# vera-module.net
KiCad netlist of a schematic drawn in EAGLE
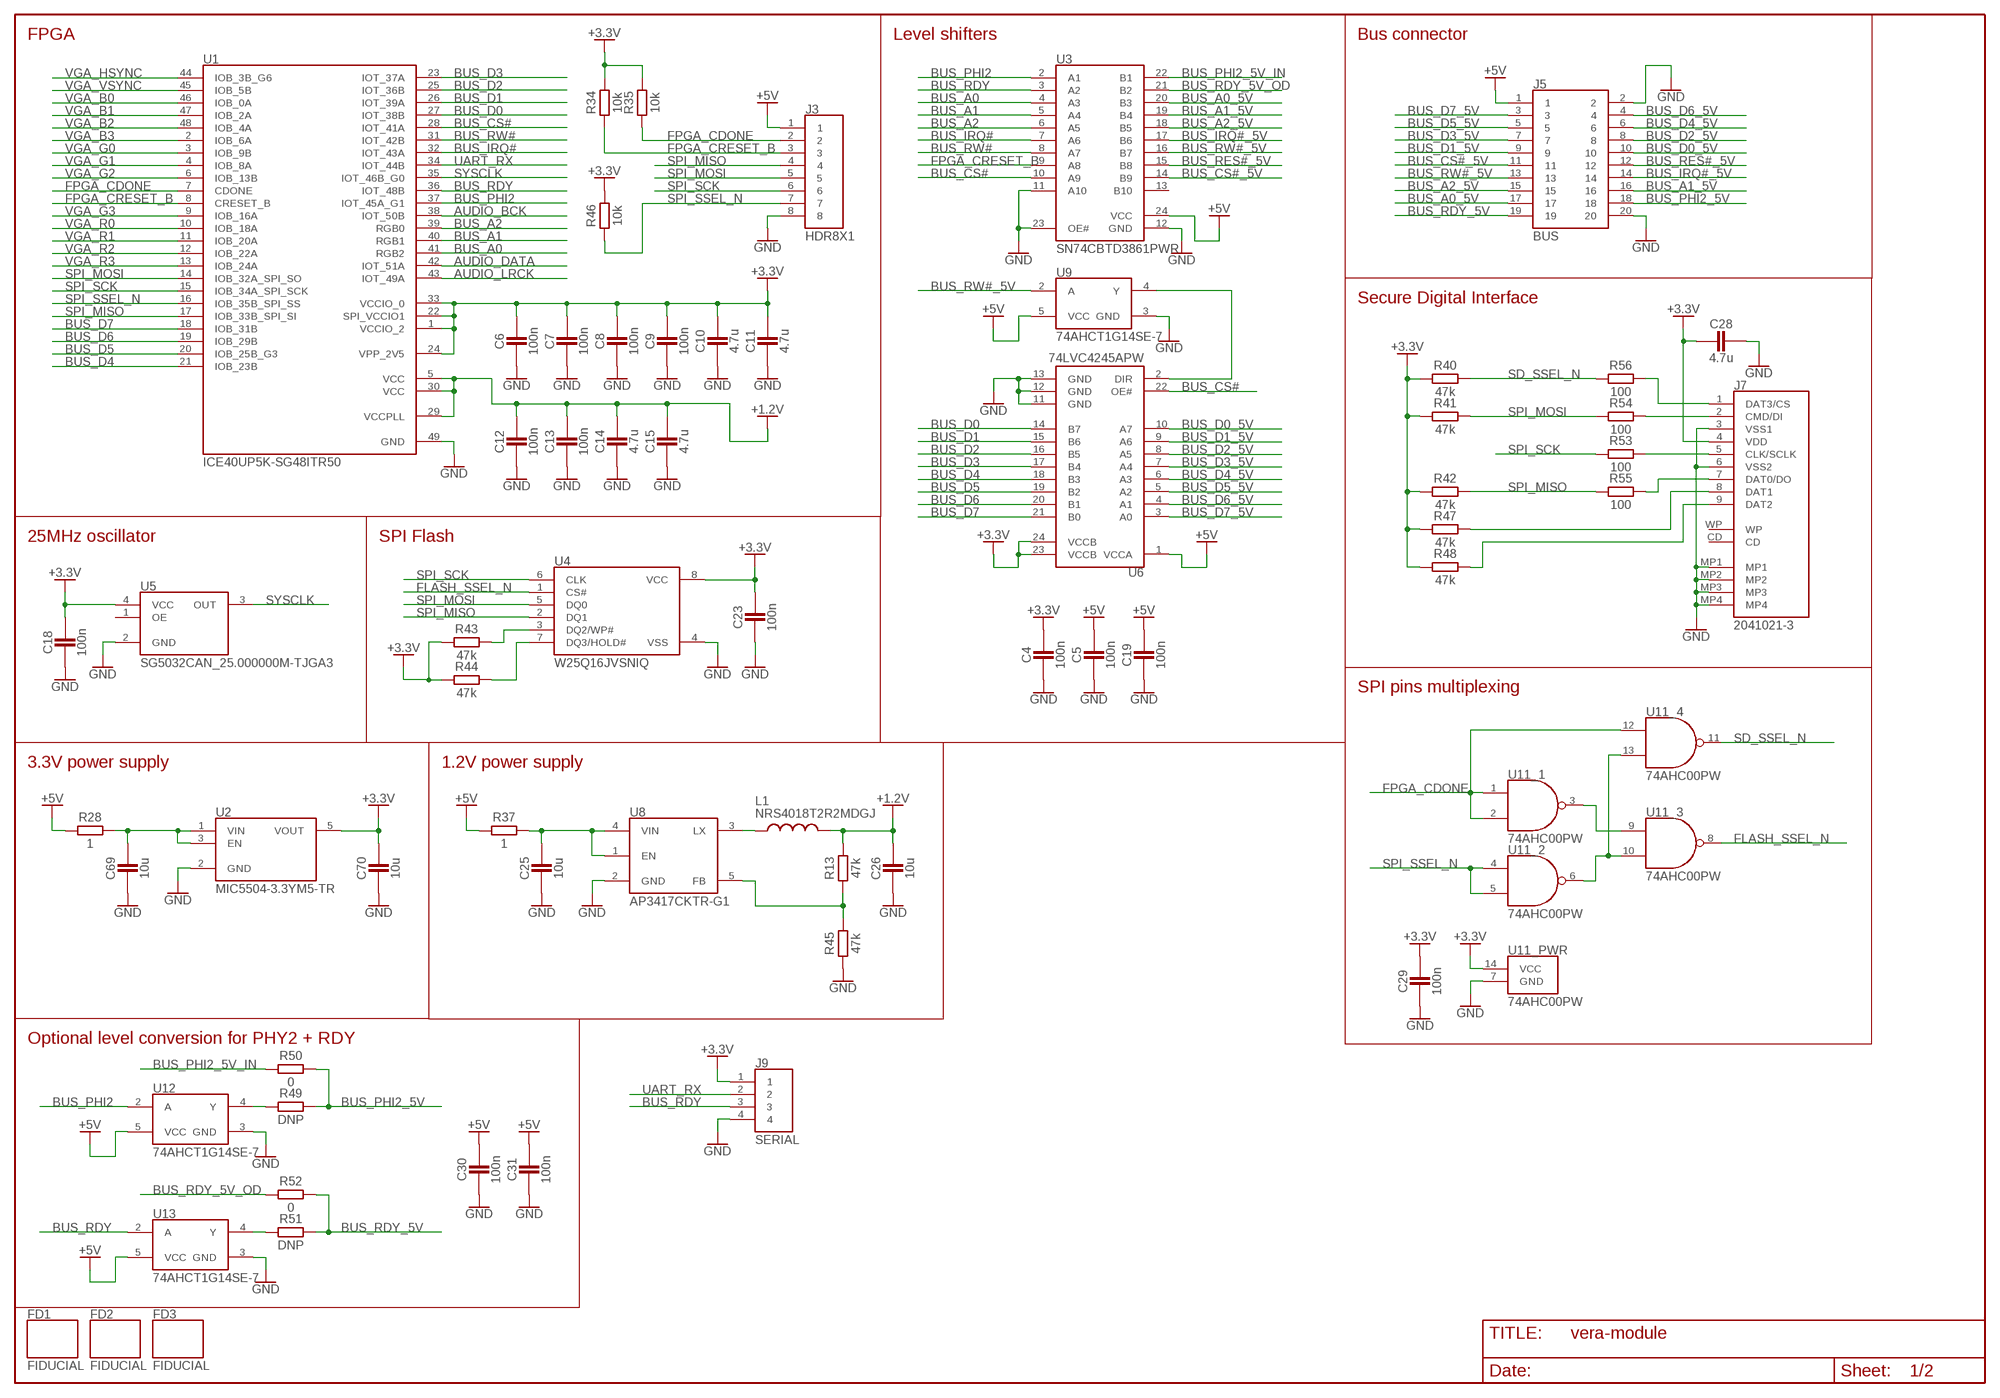
[diagram p0: schematic, sheet 1]
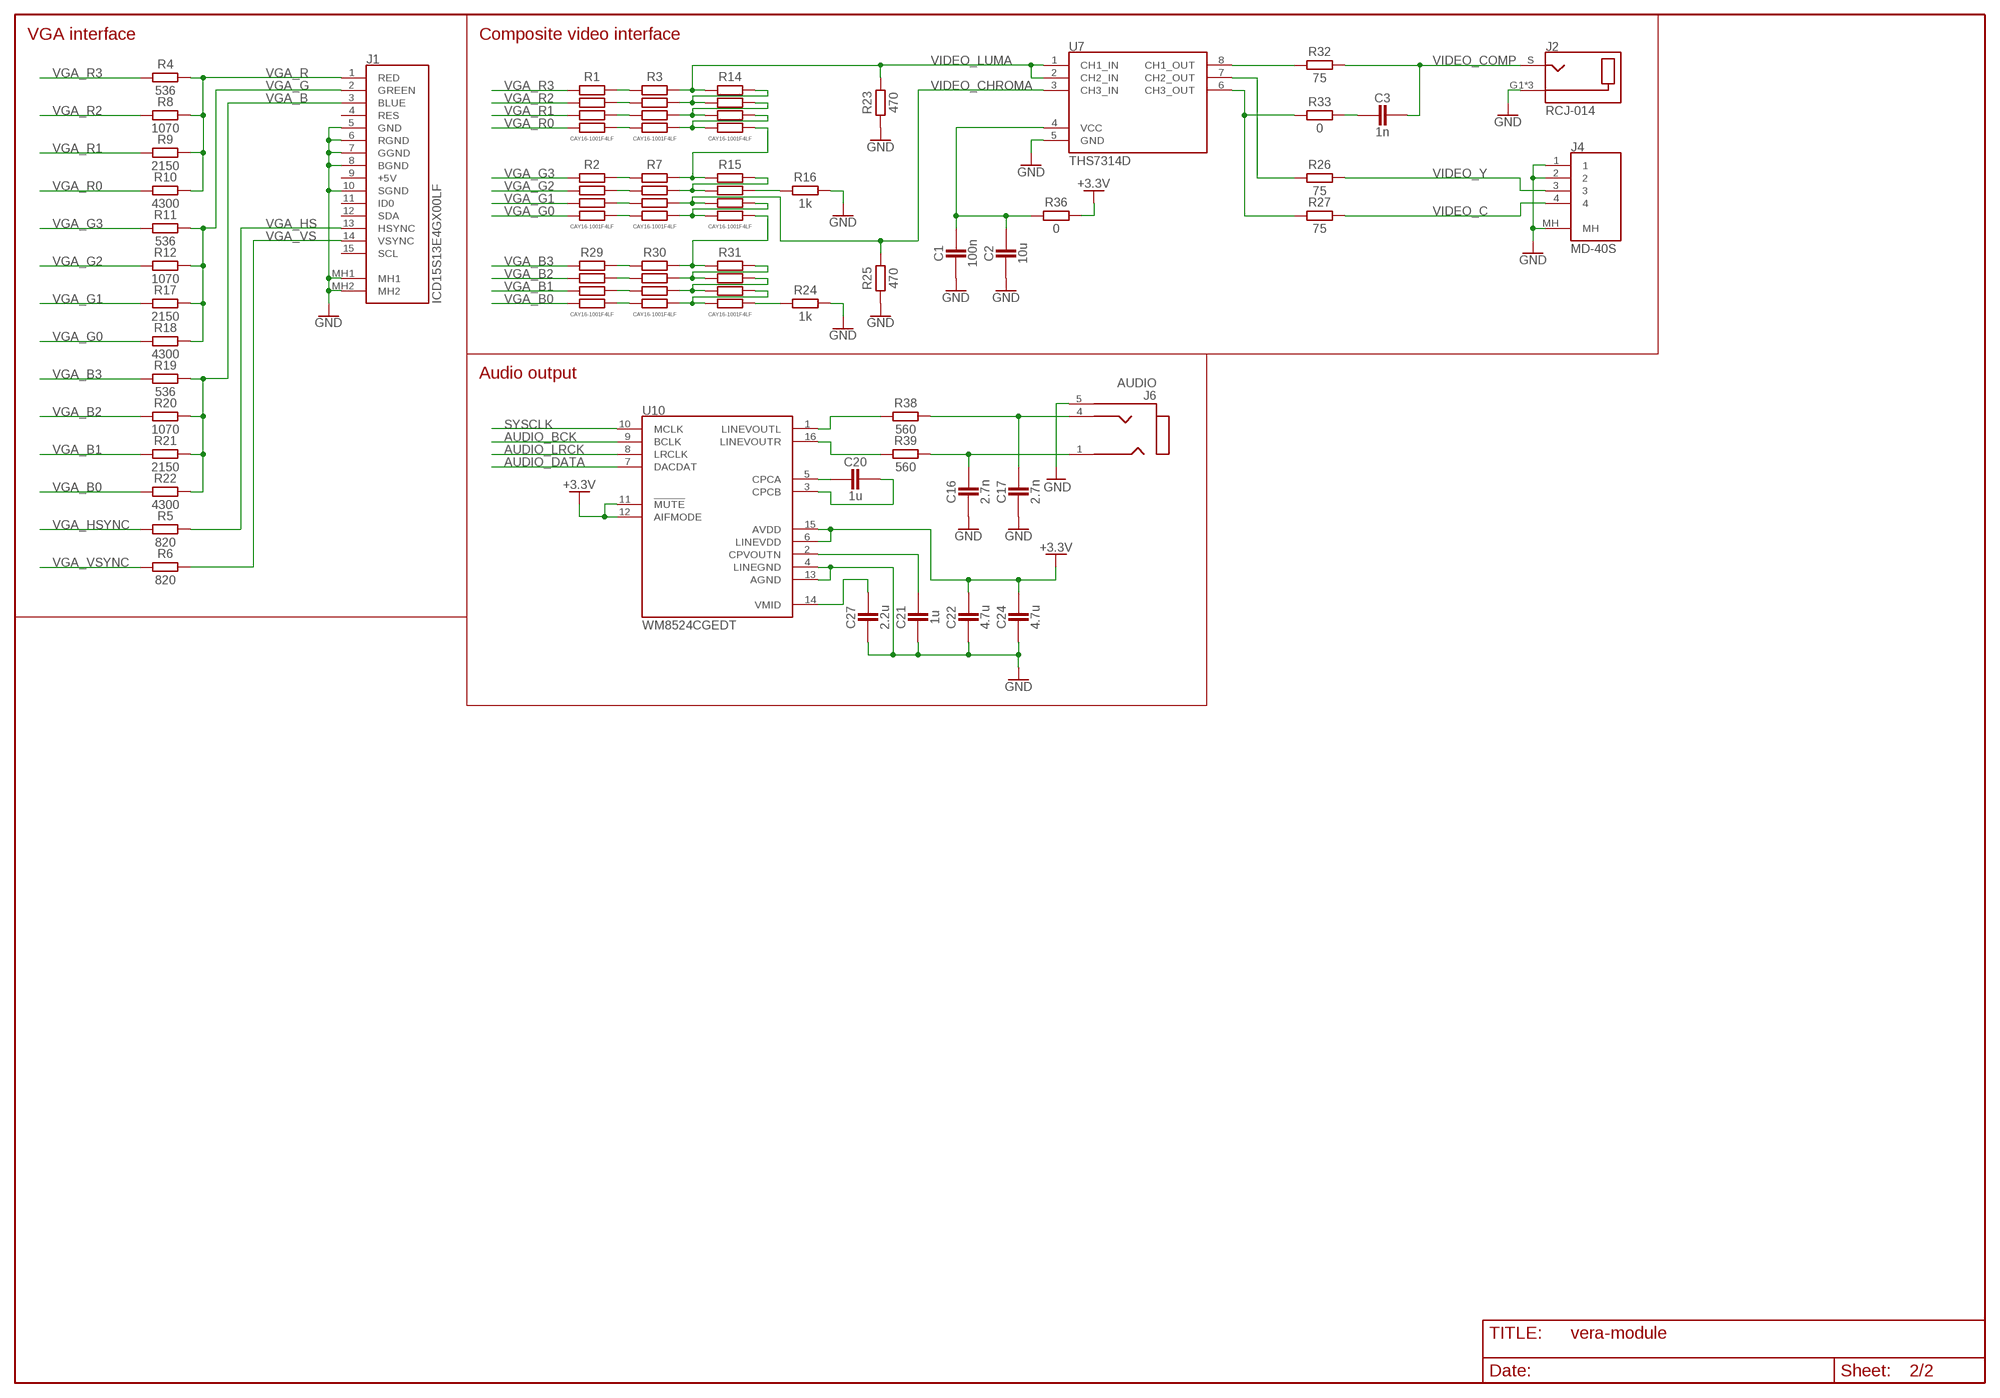
[diagram p1: schematic, sheet 2]

(export (version "E")
  (design (tool "Eeschema 10.0.6"))
  (components
    (comp (ref "C1")
      (value "100n")
      (footprint "eagle-import:C0603")
      (libsource (lib "eagle-import") (part "CAPACITOR0603"))
    )
    (comp (ref "C2")
      (value "10u")
      (footprint "eagle-import:C0805")
      (libsource (lib "eagle-import") (part "CAPACITOR0805"))
    )
    (comp (ref "C3")
      (value "1n")
      (footprint "eagle-import:C0603")
      (libsource (lib "eagle-import") (part "CAPACITOR0603"))
    )
    (comp (ref "C16")
      (value "2.7n")
      (footprint "eagle-import:C0603")
      (libsource (lib "eagle-import") (part "CAPACITOR0603"))
    )
    (comp (ref "C17")
      (value "2.7n")
      (footprint "eagle-import:C0603")
      (libsource (lib "eagle-import") (part "CAPACITOR0603"))
    )
    (comp (ref "C20")
      (value "1u")
      (footprint "eagle-import:C0603")
      (libsource (lib "eagle-import") (part "CAPACITOR0603"))
    )
    (comp (ref "C21")
      (value "1u")
      (footprint "eagle-import:C0603")
      (libsource (lib "eagle-import") (part "CAPACITOR0603"))
    )
    (comp (ref "C22")
      (value "4.7u")
      (footprint "eagle-import:C0603")
      (libsource (lib "eagle-import") (part "CAPACITOR0603"))
    )
    (comp (ref "C24")
      (value "4.7u")
      (footprint "eagle-import:C0603")
      (libsource (lib "eagle-import") (part "CAPACITOR0603"))
    )
    (comp (ref "C27")
      (value "2.2u")
      (footprint "eagle-import:C0603")
      (libsource (lib "eagle-import") (part "CAPACITOR0603"))
    )
    (comp (ref "J1")
      (value "ICD15S13E4GX00LF")
      (footprint "eagle-import:1-1734344-2")
      (libsource (lib "eagle-import") (part "ICD15S13E4GX00LF"))
    )
    (comp (ref "J2")
      (value "RCJ-014")
      (footprint "eagle-import:RCJ-01X")
      (libsource (lib "eagle-import") (part "RCJ-014"))
    )
    (comp (ref "J4")
      (value "MD-40S")
      (footprint "eagle-import:MD-40S")
      (libsource (lib "eagle-import") (part "MD-40S"))
    )
    (comp (ref "J6")
      (value "AUDIO")
      (footprint "eagle-import:35RASMT2BHNTRX")
      (libsource (lib "eagle-import") (part "35RASMT2BHNTRX"))
    )
    (comp (ref "R1")
      (value "CAY16-1001F4LF")
      (footprint "eagle-import:RA4_1206")
      (libsource (lib "eagle-import") (part "RES_ARRAY41206"))
    )
    (comp (ref "R2")
      (value "CAY16-1001F4LF")
      (footprint "eagle-import:RA4_1206")
      (libsource (lib "eagle-import") (part "RES_ARRAY41206"))
    )
    (comp (ref "R3")
      (value "CAY16-1001F4LF")
      (footprint "eagle-import:RA4_1206")
      (libsource (lib "eagle-import") (part "RES_ARRAY41206"))
    )
    (comp (ref "R4")
      (value "536")
      (footprint "eagle-import:R0603")
      (libsource (lib "eagle-import") (part "RESISTOR0603"))
    )
    (comp (ref "R5")
      (value "820")
      (footprint "eagle-import:R0603")
      (libsource (lib "eagle-import") (part "RESISTOR0603"))
    )
    (comp (ref "R6")
      (value "820")
      (footprint "eagle-import:R0603")
      (libsource (lib "eagle-import") (part "RESISTOR0603"))
    )
    (comp (ref "R7")
      (value "CAY16-1001F4LF")
      (footprint "eagle-import:RA4_1206")
      (libsource (lib "eagle-import") (part "RES_ARRAY41206"))
    )
    (comp (ref "R8")
      (value "1070")
      (footprint "eagle-import:R0603")
      (libsource (lib "eagle-import") (part "RESISTOR0603"))
    )
    (comp (ref "R9")
      (value "2150")
      (footprint "eagle-import:R0603")
      (libsource (lib "eagle-import") (part "RESISTOR0603"))
    )
    (comp (ref "R10")
      (value "4300")
      (footprint "eagle-import:R0603")
      (libsource (lib "eagle-import") (part "RESISTOR0603"))
    )
    (comp (ref "R11")
      (value "536")
      (footprint "eagle-import:R0603")
      (libsource (lib "eagle-import") (part "RESISTOR0603"))
    )
    (comp (ref "R12")
      (value "1070")
      (footprint "eagle-import:R0603")
      (libsource (lib "eagle-import") (part "RESISTOR0603"))
    )
    (comp (ref "R14")
      (value "CAY16-1001F4LF")
      (footprint "eagle-import:RA4_1206")
      (libsource (lib "eagle-import") (part "RES_ARRAY41206"))
    )
    (comp (ref "R15")
      (value "CAY16-1001F4LF")
      (footprint "eagle-import:RA4_1206")
      (libsource (lib "eagle-import") (part "RES_ARRAY41206"))
    )
    (comp (ref "R16")
      (value "1k")
      (footprint "eagle-import:R0603")
      (libsource (lib "eagle-import") (part "RESISTOR0603"))
    )
    (comp (ref "R17")
      (value "2150")
      (footprint "eagle-import:R0603")
      (libsource (lib "eagle-import") (part "RESISTOR0603"))
    )
    (comp (ref "R18")
      (value "4300")
      (footprint "eagle-import:R0603")
      (libsource (lib "eagle-import") (part "RESISTOR0603"))
    )
    (comp (ref "R19")
      (value "536")
      (footprint "eagle-import:R0603")
      (libsource (lib "eagle-import") (part "RESISTOR0603"))
    )
    (comp (ref "R20")
      (value "1070")
      (footprint "eagle-import:R0603")
      (libsource (lib "eagle-import") (part "RESISTOR0603"))
    )
    (comp (ref "R21")
      (value "2150")
      (footprint "eagle-import:R0603")
      (libsource (lib "eagle-import") (part "RESISTOR0603"))
    )
    (comp (ref "R22")
      (value "4300")
      (footprint "eagle-import:R0603")
      (libsource (lib "eagle-import") (part "RESISTOR0603"))
    )
    (comp (ref "R23")
      (value "470")
      (footprint "eagle-import:R0603")
      (libsource (lib "eagle-import") (part "RESISTOR0603"))
    )
    (comp (ref "R24")
      (value "1k")
      (footprint "eagle-import:R0603")
      (libsource (lib "eagle-import") (part "RESISTOR0603"))
    )
    (comp (ref "R25")
      (value "470")
      (footprint "eagle-import:R0603")
      (libsource (lib "eagle-import") (part "RESISTOR0603"))
    )
    (comp (ref "R26")
      (value "75")
      (footprint "eagle-import:R0603")
      (libsource (lib "eagle-import") (part "RESISTOR0603"))
    )
    (comp (ref "R27")
      (value "75")
      (footprint "eagle-import:R0603")
      (libsource (lib "eagle-import") (part "RESISTOR0603"))
    )
    (comp (ref "R29")
      (value "CAY16-1001F4LF")
      (footprint "eagle-import:RA4_1206")
      (libsource (lib "eagle-import") (part "RES_ARRAY41206"))
    )
    (comp (ref "R30")
      (value "CAY16-1001F4LF")
      (footprint "eagle-import:RA4_1206")
      (libsource (lib "eagle-import") (part "RES_ARRAY41206"))
    )
    (comp (ref "R31")
      (value "CAY16-1001F4LF")
      (footprint "eagle-import:RA4_1206")
      (libsource (lib "eagle-import") (part "RES_ARRAY41206"))
    )
    (comp (ref "R32")
      (value "75")
      (footprint "eagle-import:R0603")
      (libsource (lib "eagle-import") (part "RESISTOR0603"))
    )
    (comp (ref "R33")
      (value "0")
      (footprint "eagle-import:R0603")
      (libsource (lib "eagle-import") (part "RESISTOR0603"))
    )
    (comp (ref "R36")
      (value "0")
      (footprint "eagle-import:R0603")
      (libsource (lib "eagle-import") (part "RESISTOR0603"))
    )
    (comp (ref "R38")
      (value "560")
      (footprint "eagle-import:R0603")
      (libsource (lib "eagle-import") (part "RESISTOR0603"))
    )
    (comp (ref "R39")
      (value "560")
      (footprint "eagle-import:R0603")
      (libsource (lib "eagle-import") (part "RESISTOR0603"))
    )
    (comp (ref "U7")
      (value "THS7314D")
      (footprint "eagle-import:SOIC-8")
      (libsource (lib "eagle-import") (part "THS7314D"))
    )
    (comp (ref "U10")
      (value "WM8524CGEDT")
      (footprint "eagle-import:TSSOP-16")
      (libsource (lib "eagle-import") (part "WM8524CGEDT"))
    )
    (comp (ref "C4")
      (value "100n")
      (footprint "eagle-import:C0603")
      (libsource (lib "eagle-import") (part "CAPACITOR0603"))
    )
    (comp (ref "C5")
      (value "100n")
      (footprint "eagle-import:C0603")
      (libsource (lib "eagle-import") (part "CAPACITOR0603"))
    )
    (comp (ref "C6")
      (value "100n")
      (footprint "eagle-import:C0603")
      (libsource (lib "eagle-import") (part "CAPACITOR0603"))
    )
    (comp (ref "C7")
      (value "100n")
      (footprint "eagle-import:C0603")
      (libsource (lib "eagle-import") (part "CAPACITOR0603"))
    )
    (comp (ref "C8")
      (value "100n")
      (footprint "eagle-import:C0603")
      (libsource (lib "eagle-import") (part "CAPACITOR0603"))
    )
    (comp (ref "C9")
      (value "100n")
      (footprint "eagle-import:C0603")
      (libsource (lib "eagle-import") (part "CAPACITOR0603"))
    )
    (comp (ref "C10")
      (value "4.7u")
      (footprint "eagle-import:C0603")
      (libsource (lib "eagle-import") (part "CAPACITOR0603"))
    )
    (comp (ref "C11")
      (value "4.7u")
      (footprint "eagle-import:C0603")
      (libsource (lib "eagle-import") (part "CAPACITOR0603"))
    )
    (comp (ref "C12")
      (value "100n")
      (footprint "eagle-import:C0603")
      (libsource (lib "eagle-import") (part "CAPACITOR0603"))
    )
    (comp (ref "C13")
      (value "100n")
      (footprint "eagle-import:C0603")
      (libsource (lib "eagle-import") (part "CAPACITOR0603"))
    )
    (comp (ref "C14")
      (value "4.7u")
      (footprint "eagle-import:C0603")
      (libsource (lib "eagle-import") (part "CAPACITOR0603"))
    )
    (comp (ref "C15")
      (value "4.7u")
      (footprint "eagle-import:C0603")
      (libsource (lib "eagle-import") (part "CAPACITOR0603"))
    )
    (comp (ref "C18")
      (value "100n")
      (footprint "eagle-import:C0603")
      (libsource (lib "eagle-import") (part "CAPACITOR0603"))
    )
    (comp (ref "C19")
      (value "100n")
      (footprint "eagle-import:C0603")
      (libsource (lib "eagle-import") (part "CAPACITOR0603"))
    )
    (comp (ref "C23")
      (value "100n")
      (footprint "eagle-import:C0603")
      (libsource (lib "eagle-import") (part "CAPACITOR0603"))
    )
    (comp (ref "C25")
      (value "10u")
      (footprint "eagle-import:C0805")
      (libsource (lib "eagle-import") (part "CAPACITOR0805"))
    )
    (comp (ref "C26")
      (value "10u")
      (footprint "eagle-import:C0805")
      (libsource (lib "eagle-import") (part "CAPACITOR0805"))
    )
    (comp (ref "C28")
      (value "4.7u")
      (footprint "eagle-import:C0603")
      (libsource (lib "eagle-import") (part "CAPACITOR0603"))
    )
    (comp (ref "C29")
      (value "100n")
      (footprint "eagle-import:C0603")
      (libsource (lib "eagle-import") (part "CAPACITOR0603"))
    )
    (comp (ref "C30")
      (value "100n")
      (footprint "eagle-import:C0603")
      (libsource (lib "eagle-import") (part "CAPACITOR0603"))
    )
    (comp (ref "C31")
      (value "100n")
      (footprint "eagle-import:C0603")
      (libsource (lib "eagle-import") (part "CAPACITOR0603"))
    )
    (comp (ref "C69")
      (value "10u")
      (footprint "eagle-import:C0805")
      (libsource (lib "eagle-import") (part "CAPACITOR0805"))
    )
    (comp (ref "C70")
      (value "10u")
      (footprint "eagle-import:C0805")
      (libsource (lib "eagle-import") (part "CAPACITOR0805"))
    )
    (comp (ref "FD1")
      (value "FIDUCIAL")
      (footprint "eagle-import:FIDUCIAL")
      (libsource (lib "eagle-import") (part "FIDUCIAL"))
    )
    (comp (ref "FD2")
      (value "FIDUCIAL")
      (footprint "eagle-import:FIDUCIAL")
      (libsource (lib "eagle-import") (part "FIDUCIAL"))
    )
    (comp (ref "FD3")
      (value "FIDUCIAL")
      (footprint "eagle-import:FIDUCIAL")
      (libsource (lib "eagle-import") (part "FIDUCIAL"))
    )
    (comp (ref "J3")
      (value "HDR8X1")
      (footprint "eagle-import:HDR8X1")
      (libsource (lib "eagle-import") (part "HDR8X1"))
    )
    (comp (ref "J5")
      (value "BUS")
      (footprint "eagle-import:HDR2X10")
      (libsource (lib "eagle-import") (part "HDR2X10"))
    )
    (comp (ref "J7")
      (value "2041021-3")
      (footprint "eagle-import:2041021-3")
      (libsource (lib "eagle-import") (part "2041021-3"))
    )
    (comp (ref "J9")
      (value "SERIAL")
      (footprint "eagle-import:HDR4X1")
      (libsource (lib "eagle-import") (part "HDR4X1"))
    )
    (comp (ref "L1")
      (value "NRS4018T2R2MDGJ")
      (footprint "eagle-import:NRS4018")
      (libsource (lib "eagle-import") (part "INDUCTORNRS4018"))
    )
    (comp (ref "R13")
      (value "47k")
      (footprint "eagle-import:R0603")
      (libsource (lib "eagle-import") (part "RESISTOR0603"))
    )
    (comp (ref "R28")
      (value "1")
      (footprint "eagle-import:R0603")
      (libsource (lib "eagle-import") (part "RESISTOR0603"))
    )
    (comp (ref "R34")
      (value "10k")
      (footprint "eagle-import:R0603")
      (libsource (lib "eagle-import") (part "RESISTOR0603"))
    )
    (comp (ref "R35")
      (value "10k")
      (footprint "eagle-import:R0603")
      (libsource (lib "eagle-import") (part "RESISTOR0603"))
    )
    (comp (ref "R37")
      (value "1")
      (footprint "eagle-import:R0603")
      (libsource (lib "eagle-import") (part "RESISTOR0603"))
    )
    (comp (ref "R40")
      (value "47k")
      (footprint "eagle-import:R0603")
      (libsource (lib "eagle-import") (part "RESISTOR0603"))
    )
    (comp (ref "R41")
      (value "47k")
      (footprint "eagle-import:R0603")
      (libsource (lib "eagle-import") (part "RESISTOR0603"))
    )
    (comp (ref "R42")
      (value "47k")
      (footprint "eagle-import:R0603")
      (libsource (lib "eagle-import") (part "RESISTOR0603"))
    )
    (comp (ref "R43")
      (value "47k")
      (footprint "eagle-import:R0603")
      (libsource (lib "eagle-import") (part "RESISTOR0603"))
    )
    (comp (ref "R44")
      (value "47k")
      (footprint "eagle-import:R0603")
      (libsource (lib "eagle-import") (part "RESISTOR0603"))
    )
    (comp (ref "R45")
      (value "47k")
      (footprint "eagle-import:R0603")
      (libsource (lib "eagle-import") (part "RESISTOR0603"))
    )
    (comp (ref "R46")
      (value "10k")
      (footprint "eagle-import:R0603")
      (libsource (lib "eagle-import") (part "RESISTOR0603"))
    )
    (comp (ref "R47")
      (value "47k")
      (footprint "eagle-import:R0603")
      (libsource (lib "eagle-import") (part "RESISTOR0603"))
    )
    (comp (ref "R48")
      (value "47k")
      (footprint "eagle-import:R0603")
      (libsource (lib "eagle-import") (part "RESISTOR0603"))
    )
    (comp (ref "R49")
      (value "DNP")
      (footprint "eagle-import:R0603")
      (libsource (lib "eagle-import") (part "RESISTOR0603"))
    )
    (comp (ref "R50")
      (value "0")
      (footprint "eagle-import:R0603")
      (libsource (lib "eagle-import") (part "RESISTOR0603"))
    )
    (comp (ref "R51")
      (value "DNP")
      (footprint "eagle-import:R0603")
      (libsource (lib "eagle-import") (part "RESISTOR0603"))
    )
    (comp (ref "R52")
      (value "0")
      (footprint "eagle-import:R0603")
      (libsource (lib "eagle-import") (part "RESISTOR0603"))
    )
    (comp (ref "R53")
      (value "100")
      (footprint "eagle-import:R0603")
      (libsource (lib "eagle-import") (part "RESISTOR0603"))
    )
    (comp (ref "R54")
      (value "100")
      (footprint "eagle-import:R0603")
      (libsource (lib "eagle-import") (part "RESISTOR0603"))
    )
    (comp (ref "R55")
      (value "100")
      (footprint "eagle-import:R0603")
      (libsource (lib "eagle-import") (part "RESISTOR0603"))
    )
    (comp (ref "R56")
      (value "100")
      (footprint "eagle-import:R0603")
      (libsource (lib "eagle-import") (part "RESISTOR0603"))
    )
    (comp (ref "U1")
      (value "ICE40UP5K-SG48ITR50")
      (footprint "eagle-import:QFN-48")
      (libsource (lib "eagle-import") (part "ICE40UP5K-SG48ITR50"))
    )
    (comp (ref "U2")
      (value "MIC5504-3.3YM5-TR")
      (footprint "eagle-import:SOT-23-5")
      (libsource (lib "eagle-import") (part "MIC5504-3.3YM5-TR"))
    )
    (comp (ref "U3")
      (value "SN74CBTD3861PWR")
      (footprint "eagle-import:TSSOP-24")
      (libsource (lib "eagle-import") (part "SN74CBTD3861PWR"))
    )
    (comp (ref "U4")
      (value "W25Q16JVSNIQ")
      (footprint "eagle-import:SOIC-8")
      (libsource (lib "eagle-import") (part "QSPI_FLASHSOIC8"))
    )
    (comp (ref "U5")
      (value "SG5032CAN_25.000000M-TJGA3")
      (footprint "eagle-import:SG5032")
      (libsource (lib "eagle-import") (part "SG5032CAN_40.000000M-TJGA3"))
    )
    (comp (ref "U6")
      (value "74LVC4245APW")
      (footprint "eagle-import:TSSOP-24")
      (libsource (lib "eagle-import") (part "74LVC4245APW"))
    )
    (comp (ref "U8")
      (value "AP3417CKTR-G1")
      (footprint "eagle-import:SOT-23-5")
      (libsource (lib "eagle-import") (part "AP3417CKTR-G1"))
    )
    (comp (ref "U9")
      (value "74AHCT1G14SE-7")
      (footprint "eagle-import:TSSOP-5")
      (libsource (lib "eagle-import") (part "74AHCT1G14SE-7"))
    )
    (comp (ref "U11")
      (value "74AHC00PW")
      (footprint "eagle-import:TSSOP-14")
      (libsource (lib "eagle-import") (part "74AHC00PW"))
    )
    (comp (ref "U12")
      (value "74AHCT1G14SE-7")
      (footprint "eagle-import:TSSOP-5")
      (libsource (lib "eagle-import") (part "74AHCT1G14SE-7"))
    )
    (comp (ref "U13")
      (value "74AHCT1G14SE-7")
      (footprint "eagle-import:TSSOP-5")
      (libsource (lib "eagle-import") (part "74AHCT1G14SE-7"))
    )
  )
  (nets
    (net (code "1") (name "+1.2V") (class "Default")
      (node (ref "C12") (pin "2") (pinfunction "2_2") (pintype "passive"))
      (node (ref "C13") (pin "2") (pinfunction "2_2") (pintype "passive"))
      (node (ref "C14") (pin "2") (pinfunction "2_2") (pintype "passive"))
      (node (ref "C15") (pin "2") (pinfunction "2_2") (pintype "passive"))
      (node (ref "C26") (pin "2") (pinfunction "2_2") (pintype "passive"))
      (node (ref "L1") (pin "2") (pinfunction "2_2") (pintype "passive"))
      (node (ref "R13") (pin "2") (pinfunction "2_2") (pintype "passive"))
      (node (ref "U1") (pin "29") (pinfunction "VCCPLL_29") (pintype "passive"))
      (node (ref "U1") (pin "30") (pinfunction "VCC_30") (pintype "passive"))
      (node (ref "U1") (pin "5") (pinfunction "VCC_5") (pintype "passive"))
    )
    (net (code "2") (name "+3.3V") (class "Default")
      (node (ref "C10") (pin "2") (pinfunction "2_2") (pintype "passive"))
      (node (ref "C11") (pin "2") (pinfunction "2_2") (pintype "passive"))
      (node (ref "C18") (pin "2") (pinfunction "2_2") (pintype "passive"))
      (node (ref "C22") (pin "2") (pinfunction "2_2") (pintype "passive"))
      (node (ref "C23") (pin "2") (pinfunction "2_2") (pintype "passive"))
      (node (ref "C24") (pin "2") (pinfunction "2_2") (pintype "passive"))
      (node (ref "C28") (pin "1") (pinfunction "1_1") (pintype "passive"))
      (node (ref "C29") (pin "2") (pinfunction "2_2") (pintype "passive"))
      (node (ref "C4") (pin "2") (pinfunction "2_2") (pintype "passive"))
      (node (ref "C6") (pin "2") (pinfunction "2_2") (pintype "passive"))
      (node (ref "C7") (pin "2") (pinfunction "2_2") (pintype "passive"))
      (node (ref "C70") (pin "2") (pinfunction "2_2") (pintype "passive"))
      (node (ref "C8") (pin "2") (pinfunction "2_2") (pintype "passive"))
      (node (ref "C9") (pin "2") (pinfunction "2_2") (pintype "passive"))
      (node (ref "J7") (pin "4") (pinfunction "VDD_4") (pintype "passive"))
      (node (ref "J9") (pin "1") (pinfunction "1_1") (pintype "passive"))
      (node (ref "R34") (pin "1") (pinfunction "1_1") (pintype "passive"))
      (node (ref "R35") (pin "1") (pinfunction "1_1") (pintype "passive"))
      (node (ref "R36") (pin "2") (pinfunction "2_2") (pintype "passive"))
      (node (ref "R40") (pin "1") (pinfunction "1_1") (pintype "passive"))
      (node (ref "R41") (pin "1") (pinfunction "1_1") (pintype "passive"))
      (node (ref "R42") (pin "1") (pinfunction "1_1") (pintype "passive"))
      (node (ref "R43") (pin "1") (pinfunction "1_1") (pintype "passive"))
      (node (ref "R44") (pin "1") (pinfunction "1_1") (pintype "passive"))
      (node (ref "R46") (pin "1") (pinfunction "1_1") (pintype "passive"))
      (node (ref "R47") (pin "1") (pinfunction "1_1") (pintype "passive"))
      (node (ref "R48") (pin "1") (pinfunction "1_1") (pintype "passive"))
      (node (ref "U1") (pin "1") (pinfunction "VCCIO_2_1") (pintype "passive"))
      (node (ref "U1") (pin "22") (pinfunction "SPI_VCCIO1_22") (pintype "passive"))
      (node (ref "U1") (pin "24") (pinfunction "VPP_2V5_24") (pintype "passive"))
      (node (ref "U1") (pin "33") (pinfunction "VCCIO_0_33") (pintype "passive"))
      (node (ref "U10") (pin "11") (pinfunction "~{MUTE}_11") (pintype "passive"))
      (node (ref "U10") (pin "12") (pinfunction "AIFMODE_12") (pintype "passive"))
      (node (ref "U10") (pin "15") (pinfunction "AVDD_15") (pintype "passive"))
      (node (ref "U10") (pin "6") (pinfunction "LINEVDD_6") (pintype "passive"))
      (node (ref "U11") (pin "14") (pinfunction "VCC_14") (pintype "passive"))
      (node (ref "U2") (pin "5") (pinfunction "VOUT_5") (pintype "passive"))
      (node (ref "U4") (pin "8") (pinfunction "VCC_8") (pintype "passive"))
      (node (ref "U5") (pin "4") (pinfunction "VCC_4") (pintype "passive"))
      (node (ref "U6") (pin "23") (pinfunction "VCCB_23") (pintype "passive"))
      (node (ref "U6") (pin "24") (pinfunction "VCCB_24") (pintype "passive"))
    )
    (net (code "3") (name "+5V") (class "Default")
      (node (ref "C19") (pin "2") (pinfunction "2_2") (pintype "passive"))
      (node (ref "C30") (pin "2") (pinfunction "2_2") (pintype "passive"))
      (node (ref "C31") (pin "2") (pinfunction "2_2") (pintype "passive"))
      (node (ref "C5") (pin "2") (pinfunction "2_2") (pintype "passive"))
      (node (ref "J3") (pin "1") (pinfunction "1_1") (pintype "passive"))
      (node (ref "J5") (pin "1") (pinfunction "1_1") (pintype "passive"))
      (node (ref "R28") (pin "1") (pinfunction "1_1") (pintype "passive"))
      (node (ref "R37") (pin "1") (pinfunction "1_1") (pintype "passive"))
      (node (ref "U12") (pin "5") (pinfunction "VCC_5") (pintype "passive"))
      (node (ref "U13") (pin "5") (pinfunction "VCC_5") (pintype "passive"))
      (node (ref "U3") (pin "24") (pinfunction "VCC_24") (pintype "passive"))
      (node (ref "U6") (pin "1") (pinfunction "VCCA_1") (pintype "passive"))
      (node (ref "U9") (pin "5") (pinfunction "VCC_5") (pintype "passive"))
    )
    (net (code "4") (name "AUDIO_BCK") (class "Default")
      (node (ref "U1") (pin "38") (pinfunction "IOT_50B_38") (pintype "passive"))
      (node (ref "U10") (pin "9") (pinfunction "BCLK_9") (pintype "passive"))
    )
    (net (code "5") (name "AUDIO_DATA") (class "Default")
      (node (ref "U1") (pin "42") (pinfunction "IOT_51A_42") (pintype "passive"))
      (node (ref "U10") (pin "7") (pinfunction "DACDAT_7") (pintype "passive"))
    )
    (net (code "6") (name "AUDIO_LRCK") (class "Default")
      (node (ref "U1") (pin "43") (pinfunction "IOT_49A_43") (pintype "passive"))
      (node (ref "U10") (pin "8") (pinfunction "LRCLK_8") (pintype "passive"))
    )
    (net (code "7") (name "BUS_A0") (class "Default")
      (node (ref "U1") (pin "41") (pinfunction "RGB2_41") (pintype "passive"))
      (node (ref "U3") (pin "4") (pinfunction "A3_4") (pintype "passive"))
    )
    (net (code "8") (name "BUS_A0_5V") (class "Default")
      (node (ref "J5") (pin "17") (pinfunction "17_17") (pintype "passive"))
      (node (ref "U3") (pin "20") (pinfunction "B3_20") (pintype "passive"))
    )
    (net (code "9") (name "BUS_A1") (class "Default")
      (node (ref "U1") (pin "40") (pinfunction "RGB1_40") (pintype "passive"))
      (node (ref "U3") (pin "5") (pinfunction "A4_5") (pintype "passive"))
    )
    (net (code "10") (name "BUS_A1_5V") (class "Default")
      (node (ref "J5") (pin "16") (pinfunction "16_16") (pintype "passive"))
      (node (ref "U3") (pin "19") (pinfunction "B4_19") (pintype "passive"))
    )
    (net (code "11") (name "BUS_A2") (class "Default")
      (node (ref "U1") (pin "39") (pinfunction "RGB0_39") (pintype "passive"))
      (node (ref "U3") (pin "6") (pinfunction "A5_6") (pintype "passive"))
    )
    (net (code "12") (name "BUS_A2_5V") (class "Default")
      (node (ref "J5") (pin "15") (pinfunction "15_15") (pintype "passive"))
      (node (ref "U3") (pin "18") (pinfunction "B5_18") (pintype "passive"))
    )
    (net (code "13") (name "BUS_CS#") (class "Default")
      (node (ref "U1") (pin "28") (pinfunction "IOT_41A_28") (pintype "passive"))
      (node (ref "U3") (pin "10") (pinfunction "A9_10") (pintype "passive"))
      (node (ref "U6") (pin "22") (pinfunction "OE#_22") (pintype "passive"))
    )
    (net (code "14") (name "BUS_CS#_5V") (class "Default")
      (node (ref "J5") (pin "11") (pinfunction "11_11") (pintype "passive"))
      (node (ref "U3") (pin "14") (pinfunction "B9_14") (pintype "passive"))
    )
    (net (code "15") (name "BUS_D0") (class "Default")
      (node (ref "U1") (pin "27") (pinfunction "IOT_38B_27") (pintype "passive"))
      (node (ref "U6") (pin "14") (pinfunction "B7_14") (pintype "passive"))
    )
    (net (code "16") (name "BUS_D0_5V") (class "Default")
      (node (ref "J5") (pin "10") (pinfunction "10_10") (pintype "passive"))
      (node (ref "U6") (pin "10") (pinfunction "A7_10") (pintype "passive"))
    )
    (net (code "17") (name "BUS_D1") (class "Default")
      (node (ref "U1") (pin "26") (pinfunction "IOT_39A_26") (pintype "passive"))
      (node (ref "U6") (pin "15") (pinfunction "B6_15") (pintype "passive"))
    )
    (net (code "18") (name "BUS_D1_5V") (class "Default")
      (node (ref "J5") (pin "9") (pinfunction "9_9") (pintype "passive"))
      (node (ref "U6") (pin "9") (pinfunction "A6_9") (pintype "passive"))
    )
    (net (code "19") (name "BUS_D2") (class "Default")
      (node (ref "U1") (pin "25") (pinfunction "IOT_36B_25") (pintype "passive"))
      (node (ref "U6") (pin "16") (pinfunction "B5_16") (pintype "passive"))
    )
    (net (code "20") (name "BUS_D2_5V") (class "Default")
      (node (ref "J5") (pin "8") (pinfunction "8_8") (pintype "passive"))
      (node (ref "U6") (pin "8") (pinfunction "A5_8") (pintype "passive"))
    )
    (net (code "21") (name "BUS_D3") (class "Default")
      (node (ref "U1") (pin "23") (pinfunction "IOT_37A_23") (pintype "passive"))
      (node (ref "U6") (pin "17") (pinfunction "B4_17") (pintype "passive"))
    )
    (net (code "22") (name "BUS_D3_5V") (class "Default")
      (node (ref "J5") (pin "7") (pinfunction "7_7") (pintype "passive"))
      (node (ref "U6") (pin "7") (pinfunction "A4_7") (pintype "passive"))
    )
    (net (code "23") (name "BUS_D4") (class "Default")
      (node (ref "U1") (pin "21") (pinfunction "IOB_23B_21") (pintype "passive"))
      (node (ref "U6") (pin "18") (pinfunction "B3_18") (pintype "passive"))
    )
    (net (code "24") (name "BUS_D4_5V") (class "Default")
      (node (ref "J5") (pin "6") (pinfunction "6_6") (pintype "passive"))
      (node (ref "U6") (pin "6") (pinfunction "A3_6") (pintype "passive"))
    )
    (net (code "25") (name "BUS_D5") (class "Default")
      (node (ref "U1") (pin "20") (pinfunction "IOB_25B_G3_20") (pintype "passive"))
      (node (ref "U6") (pin "19") (pinfunction "B2_19") (pintype "passive"))
    )
    (net (code "26") (name "BUS_D5_5V") (class "Default")
      (node (ref "J5") (pin "5") (pinfunction "5_5") (pintype "passive"))
      (node (ref "U6") (pin "5") (pinfunction "A2_5") (pintype "passive"))
    )
    (net (code "27") (name "BUS_D6") (class "Default")
      (node (ref "U1") (pin "19") (pinfunction "IOB_29B_19") (pintype "passive"))
      (node (ref "U6") (pin "20") (pinfunction "B1_20") (pintype "passive"))
    )
    (net (code "28") (name "BUS_D6_5V") (class "Default")
      (node (ref "J5") (pin "4") (pinfunction "4_4") (pintype "passive"))
      (node (ref "U6") (pin "4") (pinfunction "A1_4") (pintype "passive"))
    )
    (net (code "29") (name "BUS_D7") (class "Default")
      (node (ref "U1") (pin "18") (pinfunction "IOB_31B_18") (pintype "passive"))
      (node (ref "U6") (pin "21") (pinfunction "B0_21") (pintype "passive"))
    )
    (net (code "30") (name "BUS_D7_5V") (class "Default")
      (node (ref "J5") (pin "3") (pinfunction "3_3") (pintype "passive"))
      (node (ref "U6") (pin "3") (pinfunction "A0_3") (pintype "passive"))
    )
    (net (code "31") (name "BUS_IRQ#") (class "Default")
      (node (ref "U1") (pin "32") (pinfunction "IOT_43A_32") (pintype "passive"))
      (node (ref "U3") (pin "7") (pinfunction "A6_7") (pintype "passive"))
    )
    (net (code "32") (name "BUS_IRQ#_5V") (class "Default")
      (node (ref "J5") (pin "14") (pinfunction "14_14") (pintype "passive"))
      (node (ref "U3") (pin "17") (pinfunction "B6_17") (pintype "passive"))
    )
    (net (code "33") (name "BUS_PHI2") (class "Default")
      (node (ref "U1") (pin "37") (pinfunction "IOT_45A_G1_37") (pintype "passive"))
      (node (ref "U12") (pin "2") (pinfunction "A_2") (pintype "passive"))
      (node (ref "U3") (pin "2") (pinfunction "A1_2") (pintype "passive"))
    )
    (net (code "34") (name "BUS_PHI2_5V") (class "Default")
      (node (ref "J5") (pin "18") (pinfunction "18_18") (pintype "passive"))
      (node (ref "R49") (pin "2") (pinfunction "2_2") (pintype "passive"))
      (node (ref "R50") (pin "2") (pinfunction "2_2") (pintype "passive"))
    )
    (net (code "35") (name "BUS_PHI2_5V_IN") (class "Default")
      (node (ref "R50") (pin "1") (pinfunction "1_1") (pintype "passive"))
      (node (ref "U3") (pin "22") (pinfunction "B1_22") (pintype "passive"))
    )
    (net (code "36") (name "BUS_RDY") (class "Default")
      (node (ref "J9") (pin "3") (pinfunction "3_3") (pintype "passive"))
      (node (ref "U1") (pin "36") (pinfunction "IOT_48B_36") (pintype "passive"))
      (node (ref "U13") (pin "2") (pinfunction "A_2") (pintype "passive"))
      (node (ref "U3") (pin "3") (pinfunction "A2_3") (pintype "passive"))
    )
    (net (code "37") (name "BUS_RDY_5V") (class "Default")
      (node (ref "J5") (pin "19") (pinfunction "19_19") (pintype "passive"))
      (node (ref "R51") (pin "2") (pinfunction "2_2") (pintype "passive"))
      (node (ref "R52") (pin "2") (pinfunction "2_2") (pintype "passive"))
    )
    (net (code "38") (name "BUS_RDY_5V_OD") (class "Default")
      (node (ref "R52") (pin "1") (pinfunction "1_1") (pintype "passive"))
      (node (ref "U3") (pin "21") (pinfunction "B2_21") (pintype "passive"))
    )
    (net (code "39") (name "BUS_RES#_5V") (class "Default")
      (node (ref "J5") (pin "12") (pinfunction "12_12") (pintype "passive"))
      (node (ref "U3") (pin "15") (pinfunction "B8_15") (pintype "passive"))
    )
    (net (code "40") (name "BUS_RW#") (class "Default")
      (node (ref "U1") (pin "31") (pinfunction "IOT_42B_31") (pintype "passive"))
      (node (ref "U3") (pin "8") (pinfunction "A7_8") (pintype "passive"))
    )
    (net (code "41") (name "BUS_RW#_5V") (class "Default")
      (node (ref "J5") (pin "13") (pinfunction "13_13") (pintype "passive"))
      (node (ref "U3") (pin "16") (pinfunction "B7_16") (pintype "passive"))
      (node (ref "U9") (pin "2") (pinfunction "A_2") (pintype "passive"))
    )
    (net (code "42") (name "FLASH_SSEL_N") (class "Default")
      (node (ref "U11") (pin "8") (pinfunction "Y_8") (pintype "passive"))
      (node (ref "U4") (pin "1") (pinfunction "CS#_1") (pintype "passive"))
    )
    (net (code "43") (name "FPGA_CDONE") (class "Default")
      (node (ref "J3") (pin "2") (pinfunction "2_2") (pintype "passive"))
      (node (ref "R35") (pin "2") (pinfunction "2_2") (pintype "passive"))
      (node (ref "U1") (pin "7") (pinfunction "CDONE_7") (pintype "passive"))
      (node (ref "U11") (pin "1") (pinfunction "A_1") (pintype "passive"))
      (node (ref "U11") (pin "12") (pinfunction "A_12") (pintype "passive"))
      (node (ref "U11") (pin "2") (pinfunction "B_2") (pintype "passive"))
    )
    (net (code "44") (name "FPGA_CRESET_B") (class "Default")
      (node (ref "J3") (pin "3") (pinfunction "3_3") (pintype "passive"))
      (node (ref "R34") (pin "2") (pinfunction "2_2") (pintype "passive"))
      (node (ref "U1") (pin "8") (pinfunction "CRESET_B_8") (pintype "passive"))
      (node (ref "U3") (pin "9") (pinfunction "A8_9") (pintype "passive"))
    )
    (net (code "45") (name "GND") (class "Default")
      (node (ref "C1") (pin "1") (pinfunction "1_1") (pintype "passive"))
      (node (ref "C10") (pin "1") (pinfunction "1_1") (pintype "passive"))
      (node (ref "C11") (pin "1") (pinfunction "1_1") (pintype "passive"))
      (node (ref "C12") (pin "1") (pinfunction "1_1") (pintype "passive"))
      (node (ref "C13") (pin "1") (pinfunction "1_1") (pintype "passive"))
      (node (ref "C14") (pin "1") (pinfunction "1_1") (pintype "passive"))
      (node (ref "C15") (pin "1") (pinfunction "1_1") (pintype "passive"))
      (node (ref "C16") (pin "1") (pinfunction "1_1") (pintype "passive"))
      (node (ref "C17") (pin "1") (pinfunction "1_1") (pintype "passive"))
      (node (ref "C18") (pin "1") (pinfunction "1_1") (pintype "passive"))
      (node (ref "C19") (pin "1") (pinfunction "1_1") (pintype "passive"))
      (node (ref "C2") (pin "1") (pinfunction "1_1") (pintype "passive"))
      (node (ref "C21") (pin "1") (pinfunction "1_1") (pintype "passive"))
      (node (ref "C22") (pin "1") (pinfunction "1_1") (pintype "passive"))
      (node (ref "C23") (pin "1") (pinfunction "1_1") (pintype "passive"))
      (node (ref "C24") (pin "1") (pinfunction "1_1") (pintype "passive"))
      (node (ref "C25") (pin "1") (pinfunction "1_1") (pintype "passive"))
      (node (ref "C26") (pin "1") (pinfunction "1_1") (pintype "passive"))
      (node (ref "C27") (pin "1") (pinfunction "1_1") (pintype "passive"))
      (node (ref "C28") (pin "2") (pinfunction "2_2") (pintype "passive"))
      (node (ref "C29") (pin "1") (pinfunction "1_1") (pintype "passive"))
      (node (ref "C30") (pin "1") (pinfunction "1_1") (pintype "passive"))
      (node (ref "C31") (pin "1") (pinfunction "1_1") (pintype "passive"))
      (node (ref "C4") (pin "1") (pinfunction "1_1") (pintype "passive"))
      (node (ref "C5") (pin "1") (pinfunction "1_1") (pintype "passive"))
      (node (ref "C6") (pin "1") (pinfunction "1_1") (pintype "passive"))
      (node (ref "C69") (pin "1") (pinfunction "1_1") (pintype "passive"))
      (node (ref "C7") (pin "1") (pinfunction "1_1") (pintype "passive"))
      (node (ref "C70") (pin "1") (pinfunction "1_1") (pintype "passive"))
      (node (ref "C8") (pin "1") (pinfunction "1_1") (pintype "passive"))
      (node (ref "C9") (pin "1") (pinfunction "1_1") (pintype "passive"))
      (node (ref "J1") (pin "10") (pinfunction "SGND_10") (pintype "passive"))
      (node (ref "J1") (pin "5") (pinfunction "GND_5") (pintype "passive"))
      (node (ref "J1") (pin "6") (pinfunction "RGND_6") (pintype "passive"))
      (node (ref "J1") (pin "7") (pinfunction "GGND_7") (pintype "passive"))
      (node (ref "J1") (pin "8") (pinfunction "BGND_8") (pintype "passive"))
      (node (ref "J1") (pin "MH1") (pinfunction "MH1_MH1") (pintype "passive"))
      (node (ref "J1") (pin "MH2") (pinfunction "MH2_MH2") (pintype "passive"))
      (node (ref "J2") (pin "G1") (pinfunction "G_G1") (pintype "passive"))
      (node (ref "J2") (pin "G2") (pinfunction "G_G2") (pintype "passive"))
      (node (ref "J2") (pin "G3") (pinfunction "G_G3") (pintype "passive"))
      (node (ref "J3") (pin "8") (pinfunction "8_8") (pintype "passive"))
      (node (ref "J4") (pin "1") (pinfunction "1_1") (pintype "passive"))
      (node (ref "J4") (pin "2") (pinfunction "2_2") (pintype "passive"))
      (node (ref "J4") (pin "MH") (pinfunction "MH_MH") (pintype "passive"))
      (node (ref "J5") (pin "2") (pinfunction "2_2") (pintype "passive"))
      (node (ref "J5") (pin "20") (pinfunction "20_20") (pintype "passive"))
      (node (ref "J6") (pin "5") (pinfunction "SLEEVE_5") (pintype "passive"))
      (node (ref "J7") (pin "3") (pinfunction "VSS1_3") (pintype "passive"))
      (node (ref "J7") (pin "6") (pinfunction "VSS2_6") (pintype "passive"))
      (node (ref "J7") (pin "MP1") (pinfunction "MP1_MP1") (pintype "passive"))
      (node (ref "J7") (pin "MP2") (pinfunction "MP2_MP2") (pintype "passive"))
      (node (ref "J7") (pin "MP3") (pinfunction "MP3_MP3") (pintype "passive"))
      (node (ref "J7") (pin "MP4") (pinfunction "MP4_MP4") (pintype "passive"))
      (node (ref "J9") (pin "4") (pinfunction "4_4") (pintype "passive"))
      (node (ref "R16") (pin "2") (pinfunction "2_2") (pintype "passive"))
      (node (ref "R23") (pin "1") (pinfunction "1_1") (pintype "passive"))
      (node (ref "R24") (pin "2") (pinfunction "2_2") (pintype "passive"))
      (node (ref "R25") (pin "1") (pinfunction "1_1") (pintype "passive"))
      (node (ref "R45") (pin "1") (pinfunction "1_1") (pintype "passive"))
      (node (ref "U1") (pin "49") (pinfunction "GND_49") (pintype "passive"))
      (node (ref "U10") (pin "13") (pinfunction "AGND_13") (pintype "passive"))
      (node (ref "U10") (pin "4") (pinfunction "LINEGND_4") (pintype "passive"))
      (node (ref "U11") (pin "7") (pinfunction "GND_7") (pintype "passive"))
      (node (ref "U12") (pin "3") (pinfunction "GND_3") (pintype "passive"))
      (node (ref "U13") (pin "3") (pinfunction "GND_3") (pintype "passive"))
      (node (ref "U2") (pin "2") (pinfunction "GND_2") (pintype "passive"))
      (node (ref "U3") (pin "11") (pinfunction "A10_11") (pintype "passive"))
      (node (ref "U3") (pin "12") (pinfunction "GND_12") (pintype "passive"))
      (node (ref "U3") (pin "23") (pinfunction "OE#_23") (pintype "passive"))
      (node (ref "U4") (pin "4") (pinfunction "VSS_4") (pintype "passive"))
      (node (ref "U5") (pin "2") (pinfunction "GND_2") (pintype "passive"))
      (node (ref "U6") (pin "11") (pinfunction "GND_11") (pintype "passive"))
      (node (ref "U6") (pin "12") (pinfunction "GND_12") (pintype "passive"))
      (node (ref "U6") (pin "13") (pinfunction "GND_13") (pintype "passive"))
      (node (ref "U7") (pin "5") (pinfunction "GND_5") (pintype "passive"))
      (node (ref "U8") (pin "2") (pinfunction "GND_2") (pintype "passive"))
      (node (ref "U9") (pin "3") (pinfunction "GND_3") (pintype "passive"))
    )
    (net (code "46") (name "Net-(C3-Pad1)") (class "Default")
      (node (ref "C3") (pin "1") (pinfunction "1_1") (pintype "passive"))
      (node (ref "R33") (pin "2") (pinfunction "2_2") (pintype "passive"))
    )
    (net (code "47") (name "Net-(J6-RING)") (class "Default")
      (node (ref "C16") (pin "2") (pinfunction "2_2") (pintype "passive"))
      (node (ref "J6") (pin "1") (pinfunction "RING_1") (pintype "passive"))
      (node (ref "R39") (pin "2") (pinfunction "2_2") (pintype "passive"))
    )
    (net (code "48") (name "Net-(J6-TIP)") (class "Default")
      (node (ref "C17") (pin "2") (pinfunction "2_2") (pintype "passive"))
      (node (ref "J6") (pin "4") (pinfunction "TIP_4") (pintype "passive"))
      (node (ref "R38") (pin "2") (pinfunction "2_2") (pintype "passive"))
    )
    (net (code "49") (name "Net-(J7-CLK{slash}SCLK)") (class "Default")
      (node (ref "J7") (pin "5") (pinfunction "CLK/SCLK_5") (pintype "passive"))
      (node (ref "R53") (pin "2") (pinfunction "2_2") (pintype "passive"))
    )
    (net (code "50") (name "Net-(J7-CMD{slash}DI)") (class "Default")
      (node (ref "J7") (pin "2") (pinfunction "CMD/DI_2") (pintype "passive"))
      (node (ref "R54") (pin "2") (pinfunction "2_2") (pintype "passive"))
    )
    (net (code "51") (name "Net-(J7-DAT0{slash}DO)") (class "Default")
      (node (ref "J7") (pin "7") (pinfunction "DAT0/DO_7") (pintype "passive"))
      (node (ref "R55") (pin "2") (pinfunction "2_2") (pintype "passive"))
    )
    (net (code "52") (name "Net-(J7-DAT1)") (class "Default")
      (node (ref "J7") (pin "8") (pinfunction "DAT1_8") (pintype "passive"))
      (node (ref "R47") (pin "2") (pinfunction "2_2") (pintype "passive"))
    )
    (net (code "53") (name "Net-(J7-DAT2)") (class "Default")
      (node (ref "J7") (pin "9") (pinfunction "DAT2_9") (pintype "passive"))
      (node (ref "R48") (pin "2") (pinfunction "2_2") (pintype "passive"))
    )
    (net (code "54") (name "Net-(J7-DAT3{slash}CS)") (class "Default")
      (node (ref "J7") (pin "1") (pinfunction "DAT3/CS_1") (pintype "passive"))
      (node (ref "R56") (pin "2") (pinfunction "2_2") (pintype "passive"))
    )
    (net (code "55") (name "Net-(R1-Pad1A)") (class "Default")
      (node (ref "R1") (pin "1A") (pinfunction "1A_1A") (pintype "passive"))
      (node (ref "R3") (pin "1B") (pinfunction "1B_1B") (pintype "passive"))
    )
    (net (code "56") (name "Net-(R1-Pad2A)") (class "Default")
      (node (ref "R1") (pin "2A") (pinfunction "2A_2A") (pintype "passive"))
      (node (ref "R3") (pin "2B") (pinfunction "2B_2B") (pintype "passive"))
    )
    (net (code "57") (name "Net-(R1-Pad3A)") (class "Default")
      (node (ref "R1") (pin "3A") (pinfunction "3A_3A") (pintype "passive"))
      (node (ref "R3") (pin "3B") (pinfunction "3B_3B") (pintype "passive"))
    )
    (net (code "58") (name "Net-(R1-Pad4A)") (class "Default")
      (node (ref "R1") (pin "4A") (pinfunction "4A_4A") (pintype "passive"))
      (node (ref "R3") (pin "4B") (pinfunction "4B_4B") (pintype "passive"))
    )
    (net (code "59") (name "Net-(R2-Pad1A)") (class "Default")
      (node (ref "R2") (pin "1A") (pinfunction "1A_1A") (pintype "passive"))
      (node (ref "R7") (pin "1B") (pinfunction "1B_1B") (pintype "passive"))
    )
    (net (code "60") (name "Net-(R2-Pad2A)") (class "Default")
      (node (ref "R2") (pin "2A") (pinfunction "2A_2A") (pintype "passive"))
      (node (ref "R7") (pin "2B") (pinfunction "2B_2B") (pintype "passive"))
    )
    (net (code "61") (name "Net-(R2-Pad3A)") (class "Default")
      (node (ref "R2") (pin "3A") (pinfunction "3A_3A") (pintype "passive"))
      (node (ref "R7") (pin "3B") (pinfunction "3B_3B") (pintype "passive"))
    )
    (net (code "62") (name "Net-(R2-Pad4A)") (class "Default")
      (node (ref "R2") (pin "4A") (pinfunction "4A_4A") (pintype "passive"))
      (node (ref "R7") (pin "4B") (pinfunction "4B_4B") (pintype "passive"))
    )
    (net (code "63") (name "Net-(R14-Pad1A)") (class "Default")
      (node (ref "R14") (pin "1A") (pinfunction "1A_1A") (pintype "passive"))
      (node (ref "R14") (pin "2B") (pinfunction "2B_2B") (pintype "passive"))
      (node (ref "R3") (pin "2A") (pinfunction "2A_2A") (pintype "passive"))
    )
    (net (code "64") (name "Net-(R14-Pad2A)") (class "Default")
      (node (ref "R14") (pin "2A") (pinfunction "2A_2A") (pintype "passive"))
      (node (ref "R14") (pin "3B") (pinfunction "3B_3B") (pintype "passive"))
      (node (ref "R3") (pin "3A") (pinfunction "3A_3A") (pintype "passive"))
    )
    (net (code "65") (name "Net-(R14-Pad3A)") (class "Default")
      (node (ref "R14") (pin "3A") (pinfunction "3A_3A") (pintype "passive"))
      (node (ref "R14") (pin "4B") (pinfunction "4B_4B") (pintype "passive"))
      (node (ref "R3") (pin "4A") (pinfunction "4A_4A") (pintype "passive"))
    )
    (net (code "66") (name "Net-(R14-Pad4A)") (class "Default")
      (node (ref "R14") (pin "4A") (pinfunction "4A_4A") (pintype "passive"))
      (node (ref "R15") (pin "1B") (pinfunction "1B_1B") (pintype "passive"))
      (node (ref "R7") (pin "1A") (pinfunction "1A_1A") (pintype "passive"))
    )
    (net (code "67") (name "Net-(R15-Pad1A)") (class "Default")
      (node (ref "R15") (pin "1A") (pinfunction "1A_1A") (pintype "passive"))
      (node (ref "R15") (pin "2B") (pinfunction "2B_2B") (pintype "passive"))
      (node (ref "R7") (pin "2A") (pinfunction "2A_2A") (pintype "passive"))
    )
    (net (code "68") (name "Net-(R15-Pad2A)") (class "Default")
      (node (ref "R15") (pin "2A") (pinfunction "2A_2A") (pintype "passive"))
      (node (ref "R16") (pin "1") (pinfunction "1_1") (pintype "passive"))
    )
    (net (code "69") (name "Net-(R15-Pad3A)") (class "Default")
      (node (ref "R15") (pin "3A") (pinfunction "3A_3A") (pintype "passive"))
      (node (ref "R15") (pin "4B") (pinfunction "4B_4B") (pintype "passive"))
      (node (ref "R7") (pin "4A") (pinfunction "4A_4A") (pintype "passive"))
    )
    (net (code "70") (name "Net-(R15-Pad4A)") (class "Default")
      (node (ref "R15") (pin "4A") (pinfunction "4A_4A") (pintype "passive"))
      (node (ref "R30") (pin "1A") (pinfunction "1A_1A") (pintype "passive"))
      (node (ref "R31") (pin "1B") (pinfunction "1B_1B") (pintype "passive"))
    )
    (net (code "71") (name "Net-(R24-Pad1)") (class "Default")
      (node (ref "R24") (pin "1") (pinfunction "1_1") (pintype "passive"))
      (node (ref "R31") (pin "4A") (pinfunction "4A_4A") (pintype "passive"))
    )
    (net (code "72") (name "Net-(R29-Pad1A)") (class "Default")
      (node (ref "R29") (pin "1A") (pinfunction "1A_1A") (pintype "passive"))
      (node (ref "R30") (pin "1B") (pinfunction "1B_1B") (pintype "passive"))
    )
    (net (code "73") (name "Net-(R29-Pad2A)") (class "Default")
      (node (ref "R29") (pin "2A") (pinfunction "2A_2A") (pintype "passive"))
      (node (ref "R30") (pin "2B") (pinfunction "2B_2B") (pintype "passive"))
    )
    (net (code "74") (name "Net-(R29-Pad3A)") (class "Default")
      (node (ref "R29") (pin "3A") (pinfunction "3A_3A") (pintype "passive"))
      (node (ref "R30") (pin "3B") (pinfunction "3B_3B") (pintype "passive"))
    )
    (net (code "75") (name "Net-(R29-Pad4A)") (class "Default")
      (node (ref "R29") (pin "4A") (pinfunction "4A_4A") (pintype "passive"))
      (node (ref "R30") (pin "4B") (pinfunction "4B_4B") (pintype "passive"))
    )
    (net (code "76") (name "Net-(R30-Pad2A)") (class "Default")
      (node (ref "R30") (pin "2A") (pinfunction "2A_2A") (pintype "passive"))
      (node (ref "R31") (pin "1A") (pinfunction "1A_1A") (pintype "passive"))
      (node (ref "R31") (pin "2B") (pinfunction "2B_2B") (pintype "passive"))
    )
    (net (code "77") (name "Net-(R30-Pad3A)") (class "Default")
      (node (ref "R30") (pin "3A") (pinfunction "3A_3A") (pintype "passive"))
      (node (ref "R31") (pin "2A") (pinfunction "2A_2A") (pintype "passive"))
      (node (ref "R31") (pin "3B") (pinfunction "3B_3B") (pintype "passive"))
    )
    (net (code "78") (name "Net-(R30-Pad4A)") (class "Default")
      (node (ref "R30") (pin "4A") (pinfunction "4A_4A") (pintype "passive"))
      (node (ref "R31") (pin "3A") (pinfunction "3A_3A") (pintype "passive"))
      (node (ref "R31") (pin "4B") (pinfunction "4B_4B") (pintype "passive"))
    )
    (net (code "79") (name "Net-(U2-EN)") (class "Default")
      (node (ref "C69") (pin "2") (pinfunction "2_2") (pintype "passive"))
      (node (ref "R28") (pin "2") (pinfunction "2_2") (pintype "passive"))
      (node (ref "U2") (pin "1") (pinfunction "VIN_1") (pintype "passive"))
      (node (ref "U2") (pin "3") (pinfunction "EN_3") (pintype "passive"))
    )
    (net (code "80") (name "Net-(U4-DQ2{slash}WP#)") (class "Default")
      (node (ref "R43") (pin "2") (pinfunction "2_2") (pintype "passive"))
      (node (ref "U4") (pin "3") (pinfunction "DQ2/WP#_3") (pintype "passive"))
    )
    (net (code "81") (name "Net-(U4-DQ3{slash}HOLD#)") (class "Default")
      (node (ref "R44") (pin "2") (pinfunction "2_2") (pintype "passive"))
      (node (ref "U4") (pin "7") (pinfunction "DQ3/HOLD#_7") (pintype "passive"))
    )
    (net (code "82") (name "Net-(U6-DIR)") (class "Default")
      (node (ref "U6") (pin "2") (pinfunction "DIR_2") (pintype "passive"))
      (node (ref "U9") (pin "4") (pinfunction "Y_4") (pintype "passive"))
    )
    (net (code "83") (name "Net-(U7-CH1_OUT)") (class "Default")
      (node (ref "R32") (pin "1") (pinfunction "1_1") (pintype "passive"))
      (node (ref "U7") (pin "8") (pinfunction "CH1_OUT_8") (pintype "passive"))
    )
    (net (code "84") (name "Net-(U7-CH2_OUT)") (class "Default")
      (node (ref "R26") (pin "1") (pinfunction "1_1") (pintype "passive"))
      (node (ref "U7") (pin "7") (pinfunction "CH2_OUT_7") (pintype "passive"))
    )
    (net (code "85") (name "Net-(U7-CH3_OUT)") (class "Default")
      (node (ref "R27") (pin "1") (pinfunction "1_1") (pintype "passive"))
      (node (ref "R33") (pin "1") (pinfunction "1_1") (pintype "passive"))
      (node (ref "U7") (pin "6") (pinfunction "CH3_OUT_6") (pintype "passive"))
    )
    (net (code "86") (name "Net-(U7-VCC)") (class "Default")
      (node (ref "C1") (pin "2") (pinfunction "2_2") (pintype "passive"))
      (node (ref "C2") (pin "2") (pinfunction "2_2") (pintype "passive"))
      (node (ref "R36") (pin "1") (pinfunction "1_1") (pintype "passive"))
      (node (ref "U7") (pin "4") (pinfunction "VCC_4") (pintype "passive"))
    )
    (net (code "87") (name "Net-(U8-EN)") (class "Default")
      (node (ref "C25") (pin "2") (pinfunction "2_2") (pintype "passive"))
      (node (ref "R37") (pin "2") (pinfunction "2_2") (pintype "passive"))
      (node (ref "U8") (pin "1") (pinfunction "EN_1") (pintype "passive"))
      (node (ref "U8") (pin "4") (pinfunction "VIN_4") (pintype "passive"))
    )
    (net (code "88") (name "Net-(U8-FB)") (class "Default")
      (node (ref "R13") (pin "1") (pinfunction "1_1") (pintype "passive"))
      (node (ref "R45") (pin "2") (pinfunction "2_2") (pintype "passive"))
      (node (ref "U8") (pin "5") (pinfunction "FB_5") (pintype "passive"))
    )
    (net (code "89") (name "Net-(U8-LX)") (class "Default")
      (node (ref "L1") (pin "1") (pinfunction "1_1") (pintype "passive"))
      (node (ref "U8") (pin "3") (pinfunction "LX_3") (pintype "passive"))
    )
    (net (code "90") (name "Net-(U10-CPCA)") (class "Default")
      (node (ref "C20") (pin "1") (pinfunction "1_1") (pintype "passive"))
      (node (ref "U10") (pin "5") (pinfunction "CPCA_5") (pintype "passive"))
    )
    (net (code "91") (name "Net-(U10-CPCB)") (class "Default")
      (node (ref "C20") (pin "2") (pinfunction "2_2") (pintype "passive"))
      (node (ref "U10") (pin "3") (pinfunction "CPCB_3") (pintype "passive"))
    )
    (net (code "92") (name "Net-(U10-CPVOUTN)") (class "Default")
      (node (ref "C21") (pin "2") (pinfunction "2_2") (pintype "passive"))
      (node (ref "U10") (pin "2") (pinfunction "CPVOUTN_2") (pintype "passive"))
    )
    (net (code "93") (name "Net-(U10-LINEVOUTL)") (class "Default")
      (node (ref "R38") (pin "1") (pinfunction "1_1") (pintype "passive"))
      (node (ref "U10") (pin "1") (pinfunction "LINEVOUTL_1") (pintype "passive"))
    )
    (net (code "94") (name "Net-(U10-LINEVOUTR)") (class "Default")
      (node (ref "R39") (pin "1") (pinfunction "1_1") (pintype "passive"))
      (node (ref "U10") (pin "16") (pinfunction "LINEVOUTR_16") (pintype "passive"))
    )
    (net (code "95") (name "Net-(U10-VMID)") (class "Default")
      (node (ref "C27") (pin "2") (pinfunction "2_2") (pintype "passive"))
      (node (ref "U10") (pin "14") (pinfunction "VMID_14") (pintype "passive"))
    )
    (net (code "96") (name "Net-(U11A-Y)") (class "Default")
      (node (ref "U11") (pin "3") (pinfunction "Y_3") (pintype "passive"))
      (node (ref "U11") (pin "9") (pinfunction "A_9") (pintype "passive"))
    )
    (net (code "97") (name "Net-(U11B-Y)") (class "Default")
      (node (ref "U11") (pin "10") (pinfunction "B_10") (pintype "passive"))
      (node (ref "U11") (pin "13") (pinfunction "B_13") (pintype "passive"))
      (node (ref "U11") (pin "6") (pinfunction "Y_6") (pintype "passive"))
    )
    (net (code "98") (name "Net-(U12-Y)") (class "Default")
      (node (ref "R49") (pin "1") (pinfunction "1_1") (pintype "passive"))
      (node (ref "U12") (pin "4") (pinfunction "Y_4") (pintype "passive"))
    )
    (net (code "99") (name "Net-(U13-Y)") (class "Default")
      (node (ref "R51") (pin "1") (pinfunction "1_1") (pintype "passive"))
      (node (ref "U13") (pin "4") (pinfunction "Y_4") (pintype "passive"))
    )
    (net (code "100") (name "SD_SSEL_N") (class "Default")
      (node (ref "R40") (pin "2") (pinfunction "2_2") (pintype "passive"))
      (node (ref "R56") (pin "1") (pinfunction "1_1") (pintype "passive"))
      (node (ref "U11") (pin "11") (pinfunction "Y_11") (pintype "passive"))
    )
    (net (code "101") (name "SPI_MISO") (class "Default")
      (node (ref "J3") (pin "4") (pinfunction "4_4") (pintype "passive"))
      (node (ref "R42") (pin "2") (pinfunction "2_2") (pintype "passive"))
      (node (ref "R55") (pin "1") (pinfunction "1_1") (pintype "passive"))
      (node (ref "U1") (pin "17") (pinfunction "IOB_33B_SPI_SI_17") (pintype "passive"))
      (node (ref "U4") (pin "2") (pinfunction "DQ1_2") (pintype "passive"))
    )
    (net (code "102") (name "SPI_MOSI") (class "Default")
      (node (ref "J3") (pin "5") (pinfunction "5_5") (pintype "passive"))
      (node (ref "R41") (pin "2") (pinfunction "2_2") (pintype "passive"))
      (node (ref "R54") (pin "1") (pinfunction "1_1") (pintype "passive"))
      (node (ref "U1") (pin "14") (pinfunction "IOB_32A_SPI_SO_14") (pintype "passive"))
      (node (ref "U4") (pin "5") (pinfunction "DQ0_5") (pintype "passive"))
    )
    (net (code "103") (name "SPI_SCK") (class "Default")
      (node (ref "J3") (pin "6") (pinfunction "6_6") (pintype "passive"))
      (node (ref "R53") (pin "1") (pinfunction "1_1") (pintype "passive"))
      (node (ref "U1") (pin "15") (pinfunction "IOB_34A_SPI_SCK_15") (pintype "passive"))
      (node (ref "U4") (pin "6") (pinfunction "CLK_6") (pintype "passive"))
    )
    (net (code "104") (name "SPI_SSEL_N") (class "Default")
      (node (ref "J3") (pin "7") (pinfunction "7_7") (pintype "passive"))
      (node (ref "R46") (pin "2") (pinfunction "2_2") (pintype "passive"))
      (node (ref "U1") (pin "16") (pinfunction "IOB_35B_SPI_SS_16") (pintype "passive"))
      (node (ref "U11") (pin "4") (pinfunction "A_4") (pintype "passive"))
      (node (ref "U11") (pin "5") (pinfunction "B_5") (pintype "passive"))
    )
    (net (code "105") (name "SYSCLK") (class "Default")
      (node (ref "U1") (pin "35") (pinfunction "IOT_46B_G0_35") (pintype "passive"))
      (node (ref "U10") (pin "10") (pinfunction "MCLK_10") (pintype "passive"))
      (node (ref "U5") (pin "3") (pinfunction "OUT_3") (pintype "passive"))
    )
    (net (code "106") (name "UART_RX") (class "Default")
      (node (ref "J9") (pin "2") (pinfunction "2_2") (pintype "passive"))
      (node (ref "U1") (pin "34") (pinfunction "IOT_44B_34") (pintype "passive"))
    )
    (net (code "107") (name "VGA_B") (class "Default")
      (node (ref "J1") (pin "3") (pinfunction "BLUE_3") (pintype "passive"))
      (node (ref "R19") (pin "2") (pinfunction "2_2") (pintype "passive"))
      (node (ref "R20") (pin "2") (pinfunction "2_2") (pintype "passive"))
      (node (ref "R21") (pin "2") (pinfunction "2_2") (pintype "passive"))
      (node (ref "R22") (pin "2") (pinfunction "2_2") (pintype "passive"))
    )
    (net (code "108") (name "VGA_B0") (class "Default")
      (node (ref "R22") (pin "1") (pinfunction "1_1") (pintype "passive"))
      (node (ref "R29") (pin "4B") (pinfunction "4B_4B") (pintype "passive"))
      (node (ref "U1") (pin "46") (pinfunction "IOB_0A_46") (pintype "passive"))
    )
    (net (code "109") (name "VGA_B1") (class "Default")
      (node (ref "R21") (pin "1") (pinfunction "1_1") (pintype "passive"))
      (node (ref "R29") (pin "3B") (pinfunction "3B_3B") (pintype "passive"))
      (node (ref "U1") (pin "47") (pinfunction "IOB_2A_47") (pintype "passive"))
    )
    (net (code "110") (name "VGA_B2") (class "Default")
      (node (ref "R20") (pin "1") (pinfunction "1_1") (pintype "passive"))
      (node (ref "R29") (pin "2B") (pinfunction "2B_2B") (pintype "passive"))
      (node (ref "U1") (pin "48") (pinfunction "IOB_4A_48") (pintype "passive"))
    )
    (net (code "111") (name "VGA_B3") (class "Default")
      (node (ref "R19") (pin "1") (pinfunction "1_1") (pintype "passive"))
      (node (ref "R29") (pin "1B") (pinfunction "1B_1B") (pintype "passive"))
      (node (ref "U1") (pin "2") (pinfunction "IOB_6A_2") (pintype "passive"))
    )
    (net (code "112") (name "VGA_G") (class "Default")
      (node (ref "J1") (pin "2") (pinfunction "GREEN_2") (pintype "passive"))
      (node (ref "R11") (pin "2") (pinfunction "2_2") (pintype "passive"))
      (node (ref "R12") (pin "2") (pinfunction "2_2") (pintype "passive"))
      (node (ref "R17") (pin "2") (pinfunction "2_2") (pintype "passive"))
      (node (ref "R18") (pin "2") (pinfunction "2_2") (pintype "passive"))
    )
    (net (code "113") (name "VGA_G0") (class "Default")
      (node (ref "R18") (pin "1") (pinfunction "1_1") (pintype "passive"))
      (node (ref "R2") (pin "4B") (pinfunction "4B_4B") (pintype "passive"))
      (node (ref "U1") (pin "3") (pinfunction "IOB_9B_3") (pintype "passive"))
    )
    (net (code "114") (name "VGA_G1") (class "Default")
      (node (ref "R17") (pin "1") (pinfunction "1_1") (pintype "passive"))
      (node (ref "R2") (pin "3B") (pinfunction "3B_3B") (pintype "passive"))
      (node (ref "U1") (pin "4") (pinfunction "IOB_8A_4") (pintype "passive"))
    )
    (net (code "115") (name "VGA_G2") (class "Default")
      (node (ref "R12") (pin "1") (pinfunction "1_1") (pintype "passive"))
      (node (ref "R2") (pin "2B") (pinfunction "2B_2B") (pintype "passive"))
      (node (ref "U1") (pin "6") (pinfunction "IOB_13B_6") (pintype "passive"))
    )
    (net (code "116") (name "VGA_G3") (class "Default")
      (node (ref "R11") (pin "1") (pinfunction "1_1") (pintype "passive"))
      (node (ref "R2") (pin "1B") (pinfunction "1B_1B") (pintype "passive"))
      (node (ref "U1") (pin "9") (pinfunction "IOB_16A_9") (pintype "passive"))
    )
    (net (code "117") (name "VGA_HS") (class "Default")
      (node (ref "J1") (pin "13") (pinfunction "HSYNC_13") (pintype "passive"))
      (node (ref "R5") (pin "2") (pinfunction "2_2") (pintype "passive"))
    )
    (net (code "118") (name "VGA_HSYNC") (class "Default")
      (node (ref "R5") (pin "1") (pinfunction "1_1") (pintype "passive"))
      (node (ref "U1") (pin "44") (pinfunction "IOB_3B_G6_44") (pintype "passive"))
    )
    (net (code "119") (name "VGA_R") (class "Default")
      (node (ref "J1") (pin "1") (pinfunction "RED_1") (pintype "passive"))
      (node (ref "R10") (pin "2") (pinfunction "2_2") (pintype "passive"))
      (node (ref "R4") (pin "2") (pinfunction "2_2") (pintype "passive"))
      (node (ref "R8") (pin "2") (pinfunction "2_2") (pintype "passive"))
      (node (ref "R9") (pin "2") (pinfunction "2_2") (pintype "passive"))
    )
    (net (code "120") (name "VGA_R0") (class "Default")
      (node (ref "R1") (pin "4B") (pinfunction "4B_4B") (pintype "passive"))
      (node (ref "R10") (pin "1") (pinfunction "1_1") (pintype "passive"))
      (node (ref "U1") (pin "10") (pinfunction "IOB_18A_10") (pintype "passive"))
    )
    (net (code "121") (name "VGA_R1") (class "Default")
      (node (ref "R1") (pin "3B") (pinfunction "3B_3B") (pintype "passive"))
      (node (ref "R9") (pin "1") (pinfunction "1_1") (pintype "passive"))
      (node (ref "U1") (pin "11") (pinfunction "IOB_20A_11") (pintype "passive"))
    )
    (net (code "122") (name "VGA_R2") (class "Default")
      (node (ref "R1") (pin "2B") (pinfunction "2B_2B") (pintype "passive"))
      (node (ref "R8") (pin "1") (pinfunction "1_1") (pintype "passive"))
      (node (ref "U1") (pin "12") (pinfunction "IOB_22A_12") (pintype "passive"))
    )
    (net (code "123") (name "VGA_R3") (class "Default")
      (node (ref "R1") (pin "1B") (pinfunction "1B_1B") (pintype "passive"))
      (node (ref "R4") (pin "1") (pinfunction "1_1") (pintype "passive"))
      (node (ref "U1") (pin "13") (pinfunction "IOB_24A_13") (pintype "passive"))
    )
    (net (code "124") (name "VGA_VS") (class "Default")
      (node (ref "J1") (pin "14") (pinfunction "VSYNC_14") (pintype "passive"))
      (node (ref "R6") (pin "2") (pinfunction "2_2") (pintype "passive"))
    )
    (net (code "125") (name "VGA_VSYNC") (class "Default")
      (node (ref "R6") (pin "1") (pinfunction "1_1") (pintype "passive"))
      (node (ref "U1") (pin "45") (pinfunction "IOB_5B_45") (pintype "passive"))
    )
    (net (code "126") (name "VIDEO_C") (class "Default")
      (node (ref "J4") (pin "4") (pinfunction "4_4") (pintype "passive"))
      (node (ref "R27") (pin "2") (pinfunction "2_2") (pintype "passive"))
    )
    (net (code "127") (name "VIDEO_CHROMA") (class "Default")
      (node (ref "R15") (pin "3B") (pinfunction "3B_3B") (pintype "passive"))
      (node (ref "R25") (pin "2") (pinfunction "2_2") (pintype "passive"))
      (node (ref "R7") (pin "3A") (pinfunction "3A_3A") (pintype "passive"))
      (node (ref "U7") (pin "3") (pinfunction "CH3_IN_3") (pintype "passive"))
    )
    (net (code "128") (name "VIDEO_COMP") (class "Default")
      (node (ref "C3") (pin "2") (pinfunction "2_2") (pintype "passive"))
      (node (ref "J2") (pin "S") (pinfunction "S_S") (pintype "passive"))
      (node (ref "R32") (pin "2") (pinfunction "2_2") (pintype "passive"))
    )
    (net (code "129") (name "VIDEO_LUMA") (class "Default")
      (node (ref "R14") (pin "1B") (pinfunction "1B_1B") (pintype "passive"))
      (node (ref "R23") (pin "2") (pinfunction "2_2") (pintype "passive"))
      (node (ref "R3") (pin "1A") (pinfunction "1A_1A") (pintype "passive"))
      (node (ref "U7") (pin "1") (pinfunction "CH1_IN_1") (pintype "passive"))
      (node (ref "U7") (pin "2") (pinfunction "CH2_IN_2") (pintype "passive"))
    )
    (net (code "130") (name "VIDEO_Y") (class "Default")
      (node (ref "J4") (pin "3") (pinfunction "3_3") (pintype "passive"))
      (node (ref "R26") (pin "2") (pinfunction "2_2") (pintype "passive"))
    )
    (net (code "131") (name "unconnected-(J1-+5V-Pad9)") (class "Default")
      (node (ref "J1") (pin "9") (pinfunction "+5V_9") (pintype "passive"))
    )
    (net (code "132") (name "unconnected-(J1-ID0-Pad11)") (class "Default")
      (node (ref "J1") (pin "11") (pinfunction "ID0_11") (pintype "passive"))
    )
    (net (code "133") (name "unconnected-(J1-RES-Pad4)") (class "Default")
      (node (ref "J1") (pin "4") (pinfunction "RES_4") (pintype "passive"))
    )
    (net (code "134") (name "unconnected-(J1-SCL-Pad15)") (class "Default")
      (node (ref "J1") (pin "15") (pinfunction "SCL_15") (pintype "passive"))
    )
    (net (code "135") (name "unconnected-(J1-SDA-Pad12)") (class "Default")
      (node (ref "J1") (pin "12") (pinfunction "SDA_12") (pintype "passive"))
    )
    (net (code "136") (name "unconnected-(J7-PadCD)") (class "Default")
      (node (ref "J7") (pin "CD") (pinfunction "CD_CD") (pintype "passive"))
    )
    (net (code "137") (name "unconnected-(J7-PadWP)") (class "Default")
      (node (ref "J7") (pin "WP") (pinfunction "WP_WP") (pintype "passive"))
    )
    (net (code "138") (name "unconnected-(U3-B10-Pad13)") (class "Default")
      (node (ref "U3") (pin "13") (pinfunction "B10_13") (pintype "passive"))
    )
    (net (code "139") (name "unconnected-(U5-OE-Pad1)") (class "Default")
      (node (ref "U5") (pin "1") (pinfunction "OE_1") (pintype "passive"))
    )
  )
)
